# arduino-to-headers-shield.net
KiCad netlist of a schematic drawn in Altium Designer
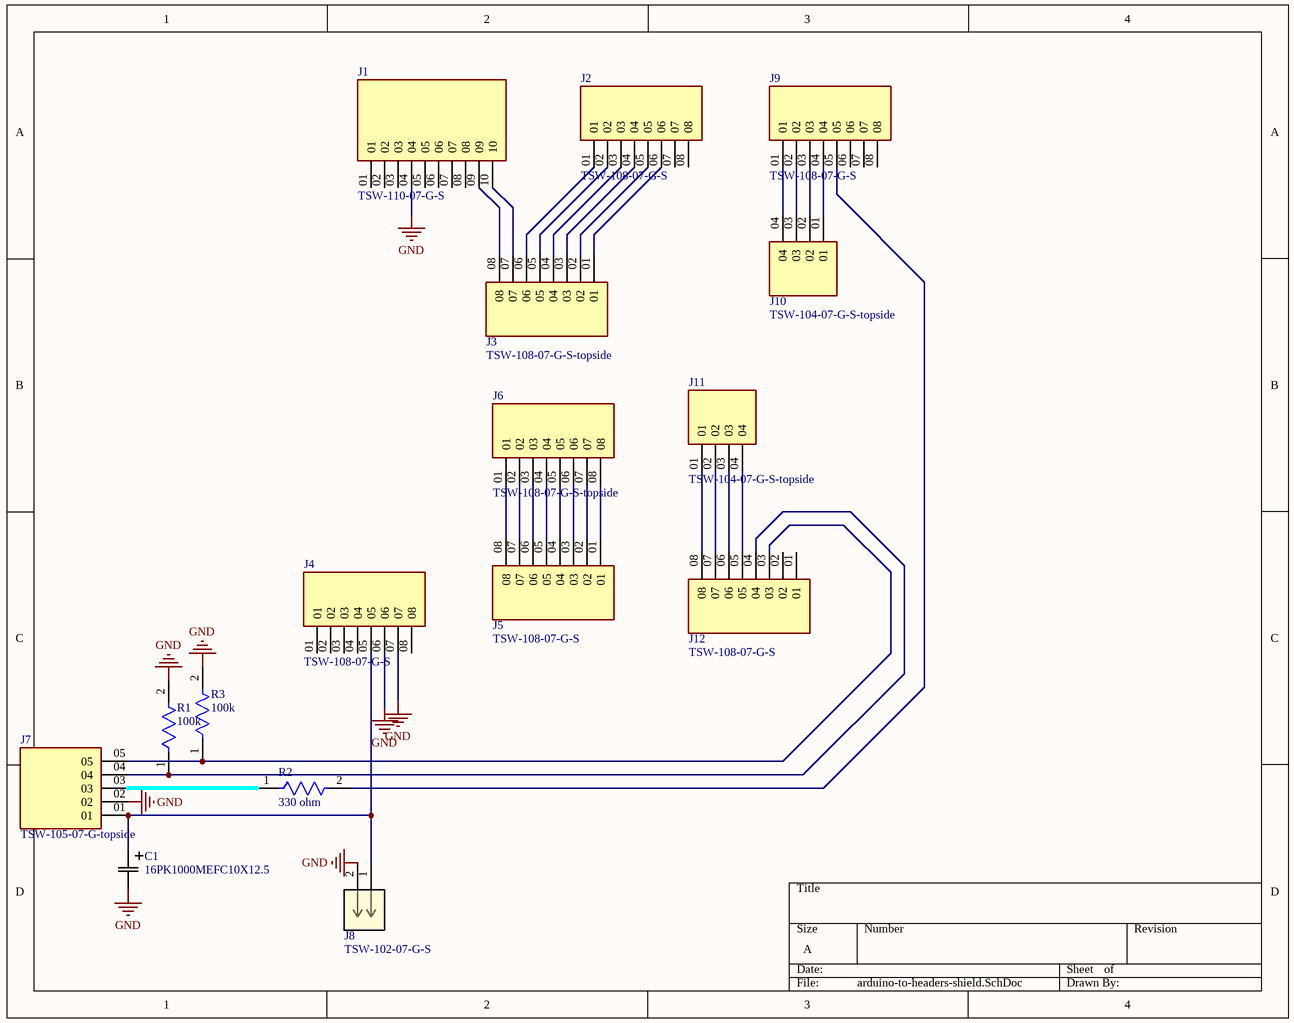
[diagram p0: arduino-to-headers-shield.SchDoc]

(export (version "E")
  (design (tool "Eeschema 10.0.6"))
  (components
    (comp (ref "C1")
      (value "16PK1000MEFC10X12.5")
      (footprint "CAP_PKPZ_10X12P5_LOW_RUB")
      (description "No Description Available")
      (fields (field (name "COPYRIGHT") "Copyright (C) 2024 Ultra Librarian. All rights reserved."))
      (libsource (lib "SchlibLafe") (part "16PK1000MEFC10X12.5"))
    )
    (comp (ref "J1")
      (value "TSW-110-07-G-S")
      (footprint "SAMTEC_TSW-110-07-G-S")
      (fields (field (name "MF") "Samtec Inc."))
      (libsource (lib "SchlibLafe") (part "TSW-110-07-G-S"))
    )
    (comp (ref "J2")
      (value "TSW-108-07-G-S")
      (footprint "SAMTEC_TSW-108-07-G-S")
      (description "TSW - Samtec 2.54mm Pin Header 10.92mm Overall Pin Length (07) - Fast Stock")
      (fields (field (name "MF") "Samtec Inc."))
      (libsource (lib "") (part "TSW-108-07-G-S_1"))
    )
    (comp (ref "J3")
      (value "TSW-108-07-G-S-topside")
      (footprint "SAMTEC_TSW-108-07-G-S-topside")
      (description "TSW - Samtec 2.54mm Pin Header 10.92mm Overall Pin Length (07) - Fast Stock")
      (fields (field (name "MF") "Samtec Inc.") (field (name "MP") "TSW-108-07-G-S"))
      (libsource (lib "SchlibLafe") (part "TSW-108-07-G-S-topside"))
    )
    (comp (ref "J4")
      (value "TSW-108-07-G-S")
      (footprint "SAMTEC_TSW-108-07-G-S")
      (description "TSW - Samtec 2.54mm Pin Header 10.92mm Overall Pin Length (07) - Fast Stock")
      (fields (field (name "MF") "Samtec Inc."))
      (libsource (lib "") (part "TSW-108-07-G-S_1"))
    )
    (comp (ref "J5")
      (value "TSW-108-07-G-S")
      (footprint "SAMTEC_TSW-108-07-G-S")
      (description "TSW - Samtec 2.54mm Pin Header 10.92mm Overall Pin Length (07) - Fast Stock")
      (fields (field (name "MF") "Samtec Inc."))
      (libsource (lib "SchlibLafe") (part "TSW-108-07-G-S"))
    )
    (comp (ref "J6")
      (value "TSW-108-07-G-S-topside")
      (footprint "SAMTEC_TSW-108-07-G-S-topside")
      (description "TSW - Samtec 2.54mm Pin Header 10.92mm Overall Pin Length (07) - Fast Stock")
      (fields (field (name "MF") "Samtec Inc.") (field (name "MP") "TSW-108-07-G-S"))
      (libsource (lib "") (part "TSW-108-07-G-S-topside_1"))
    )
    (comp (ref "J7")
      (value "TSW-105-07-G-topside")
      (footprint "SAMTEC_TSW-105-07-G-S-topside")
      (fields (field (name "MP") "TSW-105-07-G-S") (field (name "MF") "Samtec Inc."))
      (libsource (lib "SchlibLafe") (part "TSW-105-07-G-topside"))
    )
    (comp (ref "J8")
      (value "TSW-102-07-G-S")
      (footprint "TSW-102-07-G-S-topside")
      (description "No Description Available")
      (fields (field (name "COPYRIGHT") "Copyright (C) 2024 Ultra Librarian. All rights reserved."))
      (libsource (lib "SchlibLafe") (part "TSW-102-07-G-S-topside"))
    )
    (comp (ref "J9")
      (value "TSW-108-07-G-S")
      (footprint "SAMTEC_TSW-108-07-G-S")
      (description "TSW - Samtec 2.54mm Pin Header 10.92mm Overall Pin Length (07) - Fast Stock")
      (fields (field (name "MF") "Samtec Inc."))
      (libsource (lib "") (part "TSW-108-07-G-S_1"))
    )
    (comp (ref "J10")
      (value "TSW-104-07-G-S-topside")
      (footprint "SAMTEC_TSW-104-07-G-S-topside")
      (fields (field (name "MP") "altium_native_batch"))
      (libsource (lib "") (part "TSW-104-07-G-S-topside_1"))
    )
    (comp (ref "J11")
      (value "TSW-104-07-G-S-topside")
      (footprint "SAMTEC_TSW-104-07-G-S-topside")
      (fields (field (name "MP") "altium_native_batch"))
      (libsource (lib "SchlibLafe") (part "TSW-104-07-G-S-topside"))
    )
    (comp (ref "J12")
      (value "TSW-108-07-G-S")
      (footprint "SAMTEC_TSW-108-07-G-S")
      (description "TSW - Samtec 2.54mm Pin Header 10.92mm Overall Pin Length (07) - Fast Stock")
      (fields (field (name "MF") "Samtec Inc."))
      (libsource (lib "SchlibLafe") (part "TSW-108-07-G-S"))
    )
    (comp (ref "R1")
      (value "100k")
      (footprint "FP-RLR07-MFG")
      (fields (field (name "TOLERANCE") "1%"))
      (libsource (lib "Altium Content Vault") (part "1029c3af85768c4190bb7ad29bc67b5"))
    )
    (comp (ref "R2")
      (value "330 ohm")
      (footprint "FP-RLR07-MFG")
      (fields (field (name "TOLERANCE") "1%"))
      (libsource (lib "Altium Content Vault") (part "1029c3af85768c4190bb7ad29bc67b5"))
    )
    (comp (ref "R3")
      (value "100k")
      (footprint "FP-RLR07-MFG")
      (fields (field (name "TOLERANCE") "1%"))
      (libsource (lib "Altium Content Vault") (part "1029c3af85768c4190bb7ad29bc67b5"))
    )
  )
  (nets
    (net (code "1") (name "GND") (class "Default")
      (node (ref "C1") (pin "2") (pinfunction "2_2") (pintype "passive"))
      (node (ref "J1") (pin "04") (pinfunction "04_04") (pintype "passive"))
      (node (ref "J4") (pin "06") (pinfunction "06_06") (pintype "passive"))
      (node (ref "J4") (pin "07") (pinfunction "07_07") (pintype "passive"))
      (node (ref "J7") (pin "02") (pinfunction "02_02") (pintype "passive"))
      (node (ref "J8") (pin "2") (pinfunction "2_2") (pintype "passive"))
      (node (ref "R1") (pin "2") (pinfunction "2_2") (pintype "passive"))
      (node (ref "R3") (pin "2") (pinfunction "2_2") (pintype "passive"))
    )
    (net (code "2") (name "Net-(C1-Pad1)") (class "Default")
      (node (ref "C1") (pin "1") (pinfunction "1_1") (pintype "passive"))
      (node (ref "J4") (pin "05") (pinfunction "05_05") (pintype "passive"))
      (node (ref "J7") (pin "01") (pinfunction "01_01") (pintype "passive"))
      (node (ref "J8") (pin "1") (pinfunction "1_1") (pintype "passive"))
    )
    (net (code "3") (name "Net-(J1-Pad09)") (class "Default")
      (node (ref "J1") (pin "09") (pinfunction "09_09") (pintype "passive"))
      (node (ref "J3") (pin "08") (pinfunction "08_08") (pintype "passive"))
    )
    (net (code "4") (name "Net-(J1-Pad10)") (class "Default")
      (node (ref "J1") (pin "10") (pinfunction "10_10") (pintype "passive"))
      (node (ref "J3") (pin "07") (pinfunction "07_07") (pintype "passive"))
    )
    (net (code "5") (name "Net-(J2-Pad01)") (class "Default")
      (node (ref "J2") (pin "01") (pinfunction "01_01") (pintype "passive"))
      (node (ref "J3") (pin "06") (pinfunction "06_06") (pintype "passive"))
    )
    (net (code "6") (name "Net-(J2-Pad02)") (class "Default")
      (node (ref "J2") (pin "02") (pinfunction "02_02") (pintype "passive"))
      (node (ref "J3") (pin "05") (pinfunction "05_05") (pintype "passive"))
    )
    (net (code "7") (name "Net-(J2-Pad03)") (class "Default")
      (node (ref "J2") (pin "03") (pinfunction "03_03") (pintype "passive"))
      (node (ref "J3") (pin "04") (pinfunction "04_04") (pintype "passive"))
    )
    (net (code "8") (name "Net-(J2-Pad04)") (class "Default")
      (node (ref "J2") (pin "04") (pinfunction "04_04") (pintype "passive"))
      (node (ref "J3") (pin "03") (pinfunction "03_03") (pintype "passive"))
    )
    (net (code "9") (name "Net-(J2-Pad05)") (class "Default")
      (node (ref "J2") (pin "05") (pinfunction "05_05") (pintype "passive"))
      (node (ref "J3") (pin "02") (pinfunction "02_02") (pintype "passive"))
    )
    (net (code "10") (name "Net-(J2-Pad06)") (class "Default")
      (node (ref "J2") (pin "06") (pinfunction "06_06") (pintype "passive"))
      (node (ref "J3") (pin "01") (pinfunction "01_01") (pintype "passive"))
    )
    (net (code "11") (name "Net-(J5-Pad01)") (class "Default")
      (node (ref "J5") (pin "01") (pinfunction "01_01") (pintype "passive"))
      (node (ref "J6") (pin "08") (pinfunction "08_08") (pintype "passive"))
    )
    (net (code "12") (name "Net-(J5-Pad02)") (class "Default")
      (node (ref "J5") (pin "02") (pinfunction "02_02") (pintype "passive"))
      (node (ref "J6") (pin "07") (pinfunction "07_07") (pintype "passive"))
    )
    (net (code "13") (name "Net-(J5-Pad03)") (class "Default")
      (node (ref "J5") (pin "03") (pinfunction "03_03") (pintype "passive"))
      (node (ref "J6") (pin "06") (pinfunction "06_06") (pintype "passive"))
    )
    (net (code "14") (name "Net-(J5-Pad04)") (class "Default")
      (node (ref "J5") (pin "04") (pinfunction "04_04") (pintype "passive"))
      (node (ref "J6") (pin "05") (pinfunction "05_05") (pintype "passive"))
    )
    (net (code "15") (name "Net-(J5-Pad05)") (class "Default")
      (node (ref "J5") (pin "05") (pinfunction "05_05") (pintype "passive"))
      (node (ref "J6") (pin "04") (pinfunction "04_04") (pintype "passive"))
    )
    (net (code "16") (name "Net-(J5-Pad06)") (class "Default")
      (node (ref "J5") (pin "06") (pinfunction "06_06") (pintype "passive"))
      (node (ref "J6") (pin "03") (pinfunction "03_03") (pintype "passive"))
    )
    (net (code "17") (name "Net-(J5-Pad07)") (class "Default")
      (node (ref "J5") (pin "07") (pinfunction "07_07") (pintype "passive"))
      (node (ref "J6") (pin "02") (pinfunction "02_02") (pintype "passive"))
    )
    (net (code "18") (name "Net-(J5-Pad08)") (class "Default")
      (node (ref "J5") (pin "08") (pinfunction "08_08") (pintype "passive"))
      (node (ref "J6") (pin "01") (pinfunction "01_01") (pintype "passive"))
    )
    (net (code "19") (name "Net-(J7-Pad03)") (class "Default")
      (node (ref "J7") (pin "03") (pinfunction "03_03") (pintype "passive"))
      (node (ref "R2") (pin "1") (pinfunction "1_1") (pintype "passive"))
    )
    (net (code "20") (name "Net-(J9-Pad05)") (class "Default")
      (node (ref "J9") (pin "05") (pinfunction "05_05") (pintype "passive"))
      (node (ref "R2") (pin "2") (pinfunction "2_2") (pintype "passive"))
    )
    (net (code "21") (name "Net-(J10-Pad01)") (class "Default")
      (node (ref "J10") (pin "01") (pinfunction "01_01") (pintype "passive"))
      (node (ref "J9") (pin "04") (pinfunction "04_04") (pintype "passive"))
    )
    (net (code "22") (name "Net-(J10-Pad02)") (class "Default")
      (node (ref "J10") (pin "02") (pinfunction "02_02") (pintype "passive"))
      (node (ref "J9") (pin "03") (pinfunction "03_03") (pintype "passive"))
    )
    (net (code "23") (name "Net-(J10-Pad03)") (class "Default")
      (node (ref "J10") (pin "03") (pinfunction "03_03") (pintype "passive"))
      (node (ref "J9") (pin "02") (pinfunction "02_02") (pintype "passive"))
    )
    (net (code "24") (name "Net-(J10-Pad04)") (class "Default")
      (node (ref "J10") (pin "04") (pinfunction "04_04") (pintype "passive"))
      (node (ref "J9") (pin "01") (pinfunction "01_01") (pintype "passive"))
    )
    (net (code "25") (name "Net-(J11-Pad01)") (class "Default")
      (node (ref "J11") (pin "01") (pinfunction "01_01") (pintype "passive"))
      (node (ref "J12") (pin "08") (pinfunction "08_08") (pintype "passive"))
    )
    (net (code "26") (name "Net-(J11-Pad02)") (class "Default")
      (node (ref "J11") (pin "02") (pinfunction "02_02") (pintype "passive"))
      (node (ref "J12") (pin "07") (pinfunction "07_07") (pintype "passive"))
    )
    (net (code "27") (name "Net-(J11-Pad03)") (class "Default")
      (node (ref "J11") (pin "03") (pinfunction "03_03") (pintype "passive"))
      (node (ref "J12") (pin "06") (pinfunction "06_06") (pintype "passive"))
    )
    (net (code "28") (name "Net-(J11-Pad04)") (class "Default")
      (node (ref "J11") (pin "04") (pinfunction "04_04") (pintype "passive"))
      (node (ref "J12") (pin "05") (pinfunction "05_05") (pintype "passive"))
    )
    (net (code "29") (name "Net-(J12-Pad03)") (class "Default")
      (node (ref "J12") (pin "03") (pinfunction "03_03") (pintype "passive"))
      (node (ref "J7") (pin "05") (pinfunction "05_05") (pintype "passive"))
      (node (ref "R3") (pin "1") (pinfunction "1_1") (pintype "passive"))
    )
    (net (code "30") (name "Net-(J12-Pad04)") (class "Default")
      (node (ref "J12") (pin "04") (pinfunction "04_04") (pintype "passive"))
      (node (ref "J7") (pin "04") (pinfunction "04_04") (pintype "passive"))
      (node (ref "R1") (pin "1") (pinfunction "1_1") (pintype "passive"))
    )
    (net (code "31") (name "unconnected-(J1-Pad01)") (class "Default")
      (node (ref "J1") (pin "01") (pinfunction "01_01") (pintype "passive"))
    )
    (net (code "32") (name "unconnected-(J1-Pad02)") (class "Default")
      (node (ref "J1") (pin "02") (pinfunction "02_02") (pintype "passive"))
    )
    (net (code "33") (name "unconnected-(J1-Pad03)") (class "Default")
      (node (ref "J1") (pin "03") (pinfunction "03_03") (pintype "passive"))
    )
    (net (code "34") (name "unconnected-(J1-Pad05)") (class "Default")
      (node (ref "J1") (pin "05") (pinfunction "05_05") (pintype "passive"))
    )
    (net (code "35") (name "unconnected-(J1-Pad06)") (class "Default")
      (node (ref "J1") (pin "06") (pinfunction "06_06") (pintype "passive"))
    )
    (net (code "36") (name "unconnected-(J1-Pad07)") (class "Default")
      (node (ref "J1") (pin "07") (pinfunction "07_07") (pintype "passive"))
    )
    (net (code "37") (name "unconnected-(J1-Pad08)") (class "Default")
      (node (ref "J1") (pin "08") (pinfunction "08_08") (pintype "passive"))
    )
    (net (code "38") (name "unconnected-(J2-Pad07)") (class "Default")
      (node (ref "J2") (pin "07") (pinfunction "07_07") (pintype "passive"))
    )
    (net (code "39") (name "unconnected-(J2-Pad08)") (class "Default")
      (node (ref "J2") (pin "08") (pinfunction "08_08") (pintype "passive"))
    )
    (net (code "40") (name "unconnected-(J4-Pad01)") (class "Default")
      (node (ref "J4") (pin "01") (pinfunction "01_01") (pintype "passive"))
    )
    (net (code "41") (name "unconnected-(J4-Pad02)") (class "Default")
      (node (ref "J4") (pin "02") (pinfunction "02_02") (pintype "passive"))
    )
    (net (code "42") (name "unconnected-(J4-Pad03)") (class "Default")
      (node (ref "J4") (pin "03") (pinfunction "03_03") (pintype "passive"))
    )
    (net (code "43") (name "unconnected-(J4-Pad04)") (class "Default")
      (node (ref "J4") (pin "04") (pinfunction "04_04") (pintype "passive"))
    )
    (net (code "44") (name "unconnected-(J4-Pad08)") (class "Default")
      (node (ref "J4") (pin "08") (pinfunction "08_08") (pintype "passive"))
    )
    (net (code "45") (name "unconnected-(J9-Pad06)") (class "Default")
      (node (ref "J9") (pin "06") (pinfunction "06_06") (pintype "passive"))
    )
    (net (code "46") (name "unconnected-(J9-Pad07)") (class "Default")
      (node (ref "J9") (pin "07") (pinfunction "07_07") (pintype "passive"))
    )
    (net (code "47") (name "unconnected-(J9-Pad08)") (class "Default")
      (node (ref "J9") (pin "08") (pinfunction "08_08") (pintype "passive"))
    )
    (net (code "48") (name "unconnected-(J12-Pad01)") (class "Default")
      (node (ref "J12") (pin "01") (pinfunction "01_01") (pintype "passive"))
    )
    (net (code "49") (name "unconnected-(J12-Pad02)") (class "Default")
      (node (ref "J12") (pin "02") (pinfunction "02_02") (pintype "passive"))
    )
  )
)
